# Fabric_IO.net
KiCad netlist of a schematic drawn in Altium Designer
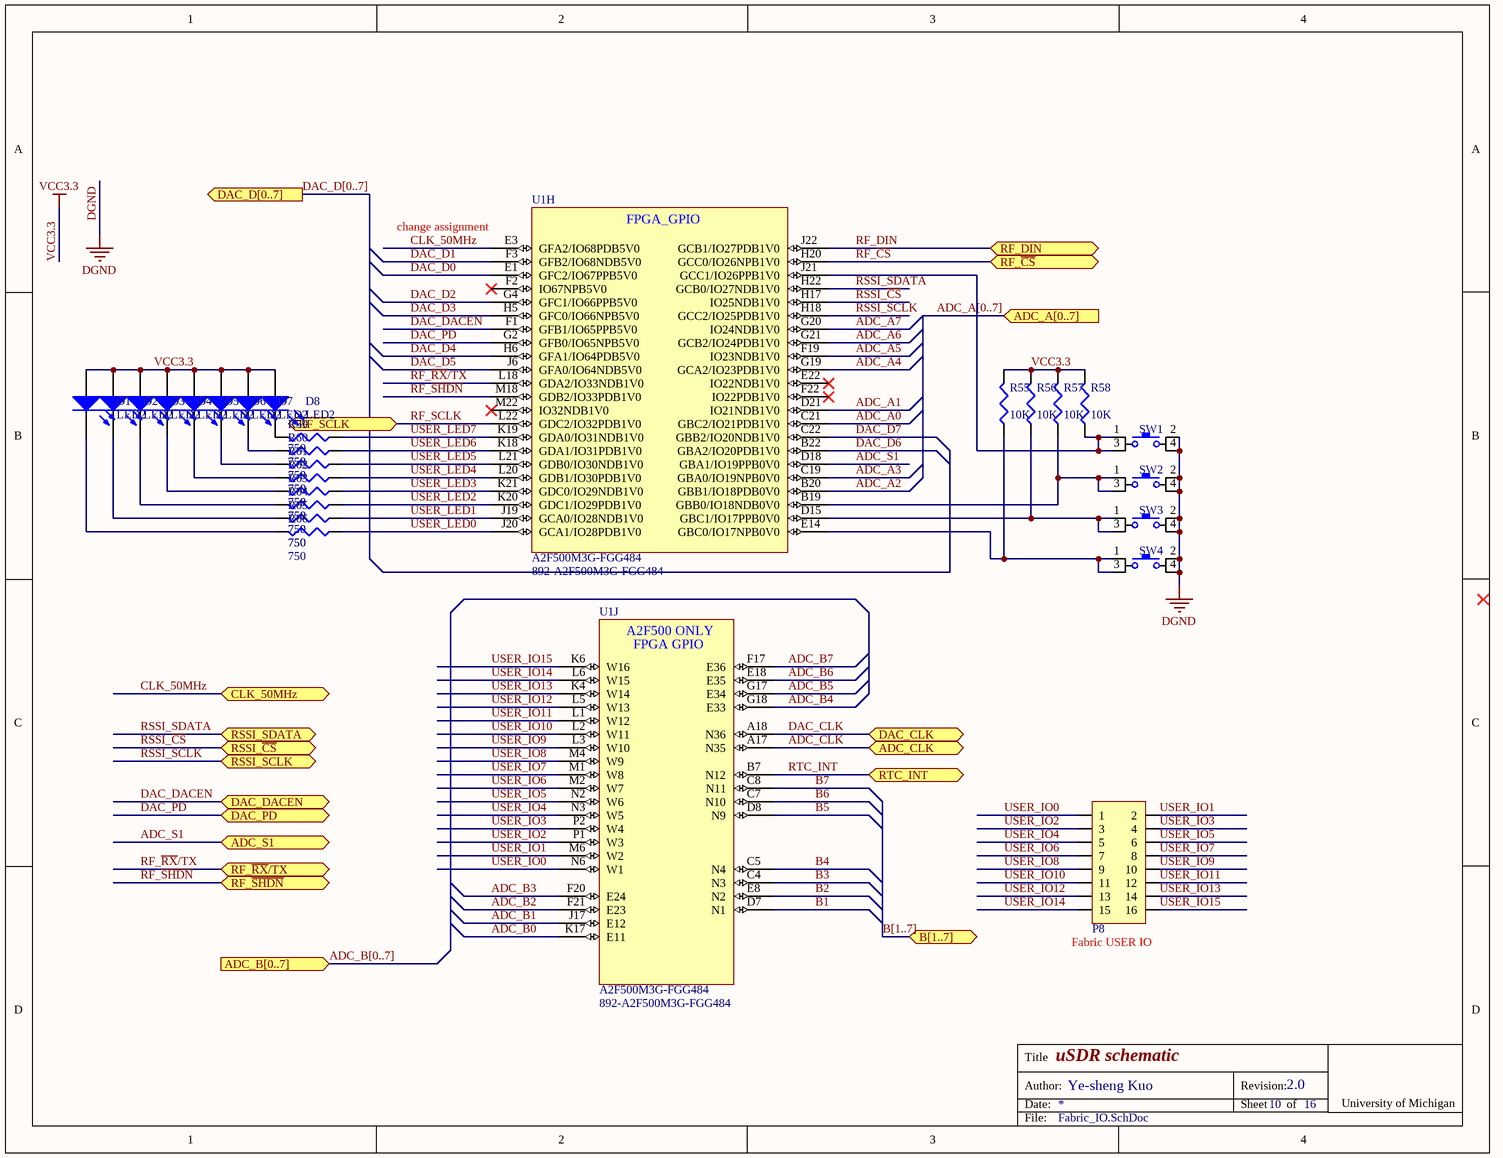
[diagram p0: Fabric_IO.SchDoc]

(export (version "E")
  (design (tool "Eeschema 10.0.6"))
  (components
    (comp (ref "D1")
      (value "LED2")
      (footprint "1608[0603]")
      (description "Typical RED, GREEN, YELLOW, AMBER GaAs LED")
      (fields (field (name "PUBLISHER") "Altium Limited"))
      (libsource (lib "Miscellaneous Devices") (part "LED Red"))
    )
    (comp (ref "D2")
      (value "LED2")
      (footprint "1608[0603]")
      (description "Typical RED, GREEN, YELLOW, AMBER GaAs LED")
      (fields (field (name "PUBLISHER") "Altium Limited"))
      (libsource (lib "Miscellaneous Devices") (part "LED Red"))
    )
    (comp (ref "D3")
      (value "LED2")
      (footprint "1608[0603]")
      (description "Typical RED, GREEN, YELLOW, AMBER GaAs LED")
      (fields (field (name "PUBLISHER") "Altium Limited"))
      (libsource (lib "Miscellaneous Devices") (part "LED Red"))
    )
    (comp (ref "D4")
      (value "LED2")
      (footprint "1608[0603]")
      (description "Typical RED, GREEN, YELLOW, AMBER GaAs LED")
      (fields (field (name "PUBLISHER") "Altium Limited"))
      (libsource (lib "Miscellaneous Devices") (part "LED Red"))
    )
    (comp (ref "D5")
      (value "LED2")
      (footprint "1608[0603]")
      (description "Typical RED, GREEN, YELLOW, AMBER GaAs LED")
      (fields (field (name "PUBLISHER") "Altium Limited"))
      (libsource (lib "Miscellaneous Devices") (part "LED Red"))
    )
    (comp (ref "D6")
      (value "LED2")
      (footprint "1608[0603]")
      (description "Typical RED, GREEN, YELLOW, AMBER GaAs LED")
      (fields (field (name "PUBLISHER") "Altium Limited"))
      (libsource (lib "Miscellaneous Devices") (part "LED Red"))
    )
    (comp (ref "D7")
      (value "LED2")
      (footprint "1608[0603]")
      (description "Typical RED, GREEN, YELLOW, AMBER GaAs LED")
      (fields (field (name "PUBLISHER") "Altium Limited"))
      (libsource (lib "Miscellaneous Devices") (part "LED Red"))
    )
    (comp (ref "D8")
      (value "LED2")
      (footprint "1608[0603]")
      (description "Typical RED, GREEN, YELLOW, AMBER GaAs LED")
      (fields (field (name "PUBLISHER") "Altium Limited"))
      (libsource (lib "Miscellaneous Devices") (part "LED Red"))
    )
    (comp (ref "P8")
      (value "2 x 8 header")
      (footprint "2x8 header")
      (description "100 mils standard header")
      (libsource (lib "SDR") (part "2 x 8 header"))
    )
    (comp (ref "R55")
      (value "10K")
      (footprint "0402")
      (description "Resistor")
      (fields (field (name "PUBLISHER") "Altium Limited"))
      (libsource (lib "Miscellaneous Devices") (part "Res3"))
    )
    (comp (ref "R56")
      (value "10K")
      (footprint "0402")
      (description "Resistor")
      (fields (field (name "PUBLISHER") "Altium Limited"))
      (libsource (lib "Miscellaneous Devices") (part "Res3"))
    )
    (comp (ref "R57")
      (value "10K")
      (footprint "0402")
      (description "Resistor")
      (fields (field (name "PUBLISHER") "Altium Limited"))
      (libsource (lib "Miscellaneous Devices") (part "Res3"))
    )
    (comp (ref "R58")
      (value "10K")
      (footprint "0402")
      (description "Resistor")
      (fields (field (name "PUBLISHER") "Altium Limited"))
      (libsource (lib "Miscellaneous Devices") (part "Res3"))
    )
    (comp (ref "R59")
      (value "750")
      (footprint "0402")
      (description "Resistor")
      (fields (field (name "ALTIUM_VALUE") "750") (field (name "PUBLISHER") "Altium Limited"))
      (libsource (lib "Miscellaneous Devices") (part "Res3"))
    )
    (comp (ref "R60")
      (value "750")
      (footprint "0402")
      (description "Resistor")
      (fields (field (name "ALTIUM_VALUE") "750") (field (name "PUBLISHER") "Altium Limited"))
      (libsource (lib "Miscellaneous Devices") (part "Res3"))
    )
    (comp (ref "R61")
      (value "750")
      (footprint "0402")
      (description "Resistor")
      (fields (field (name "ALTIUM_VALUE") "750") (field (name "PUBLISHER") "Altium Limited"))
      (libsource (lib "Miscellaneous Devices") (part "Res3"))
    )
    (comp (ref "R62")
      (value "750")
      (footprint "0402")
      (description "Resistor")
      (fields (field (name "ALTIUM_VALUE") "750") (field (name "PUBLISHER") "Altium Limited"))
      (libsource (lib "Miscellaneous Devices") (part "Res3"))
    )
    (comp (ref "R63")
      (value "750")
      (footprint "0402")
      (description "Resistor")
      (fields (field (name "ALTIUM_VALUE") "750") (field (name "PUBLISHER") "Altium Limited"))
      (libsource (lib "Miscellaneous Devices") (part "Res3"))
    )
    (comp (ref "R64")
      (value "750")
      (footprint "0402")
      (description "Resistor")
      (fields (field (name "ALTIUM_VALUE") "750") (field (name "PUBLISHER") "Altium Limited"))
      (libsource (lib "Miscellaneous Devices") (part "Res3"))
    )
    (comp (ref "R65")
      (value "750")
      (footprint "0402")
      (description "Resistor")
      (fields (field (name "ALTIUM_VALUE") "750") (field (name "PUBLISHER") "Altium Limited"))
      (libsource (lib "Miscellaneous Devices") (part "Res3"))
    )
    (comp (ref "R66")
      (value "750")
      (footprint "0402")
      (description "Resistor")
      (fields (field (name "ALTIUM_VALUE") "750") (field (name "PUBLISHER") "Altium Limited"))
      (libsource (lib "Miscellaneous Devices") (part "Res3"))
    )
    (comp (ref "SW1")
      (value "Switch 4-lead")
      (footprint "KSC403")
      (description "Switch")
      (libsource (lib "SDR") (part "Switch 4-lead"))
    )
    (comp (ref "SW2")
      (value "Switch 4-lead")
      (footprint "KSC403")
      (description "Switch")
      (libsource (lib "SDR") (part "Switch 4-lead"))
    )
    (comp (ref "SW3")
      (value "Switch 4-lead")
      (footprint "KSC403")
      (description "Switch")
      (libsource (lib "SDR") (part "Switch 4-lead"))
    )
    (comp (ref "SW4")
      (value "Switch 4-lead")
      (footprint "KSC403")
      (description "Switch")
      (libsource (lib "SDR") (part "Switch 4-lead"))
    )
    (comp (ref "U1")
      (value "A2F500M3G-FGG484")
      (footprint "BGA100P22X22-484N")
      (description "FPGA - Field Programmable Gate Array 500K System Gates")
      (fields (field (name "SUPPLIER PART NUMBER 1") "892-A2F500M3G-FGG484"))
      (libsource (lib "SDR") (part "F2-200_500-FGG484_1"))
    )
  )
  (nets
    (net (code "1") (name "/ADC_A0") (class "Default")
      (node (ref "U1") (pin "C21") (pinfunction "GBC2/IO21PDB1V0_C21") (pintype "bidirectional"))
    )
    (net (code "2") (name "/ADC_A1") (class "Default")
      (node (ref "U1") (pin "D21") (pinfunction "IO21NDB1V0_D21") (pintype "bidirectional"))
    )
    (net (code "3") (name "/ADC_A2") (class "Default")
      (node (ref "U1") (pin "B20") (pinfunction "GBB1/IO18PDB0V0_B20") (pintype "bidirectional"))
    )
    (net (code "4") (name "/ADC_A3") (class "Default")
      (node (ref "U1") (pin "C19") (pinfunction "GBA0/IO19NPB0V0_C19") (pintype "bidirectional"))
    )
    (net (code "5") (name "/ADC_A4") (class "Default")
      (node (ref "U1") (pin "G19") (pinfunction "GCA2/IO23PDB1V0_G19") (pintype "bidirectional"))
    )
    (net (code "6") (name "/ADC_A5") (class "Default")
      (node (ref "U1") (pin "F19") (pinfunction "IO23NDB1V0_F19") (pintype "bidirectional"))
    )
    (net (code "7") (name "/ADC_A6") (class "Default")
      (node (ref "U1") (pin "G21") (pinfunction "GCB2/IO24PDB1V0_G21") (pintype "bidirectional"))
    )
    (net (code "8") (name "/ADC_A7") (class "Default")
      (node (ref "U1") (pin "G20") (pinfunction "IO24NDB1V0_G20") (pintype "bidirectional"))
    )
    (net (code "10") (name "/ADC_B0") (class "Default")
      (node (ref "U1") (pin "K17") (pinfunction "E11_K17") (pintype "bidirectional"))
    )
    (net (code "11") (name "/ADC_B1") (class "Default")
      (node (ref "U1") (pin "J17") (pinfunction "E12_J17") (pintype "bidirectional"))
    )
    (net (code "12") (name "/ADC_B2") (class "Default")
      (node (ref "U1") (pin "F21") (pinfunction "E23_F21") (pintype "bidirectional"))
    )
    (net (code "13") (name "/ADC_B3") (class "Default")
      (node (ref "U1") (pin "F20") (pinfunction "E24_F20") (pintype "bidirectional"))
    )
    (net (code "14") (name "/ADC_B4") (class "Default")
      (node (ref "U1") (pin "G18") (pinfunction "E33_G18") (pintype "bidirectional"))
    )
    (net (code "15") (name "/ADC_B5") (class "Default")
      (node (ref "U1") (pin "G17") (pinfunction "E34_G17") (pintype "bidirectional"))
    )
    (net (code "16") (name "/ADC_B6") (class "Default")
      (node (ref "U1") (pin "E18") (pinfunction "E35_E18") (pintype "bidirectional"))
    )
    (net (code "17") (name "/ADC_B7") (class "Default")
      (node (ref "U1") (pin "F17") (pinfunction "E36_F17") (pintype "bidirectional"))
    )
    (net (code "19") (name "/ADC_CLK") (class "Default")
      (node (ref "U1") (pin "A17") (pinfunction "N35_A17") (pintype "bidirectional"))
    )
    (net (code "20") (name "/ADC_S1") (class "Default")
      (node (ref "U1") (pin "D18") (pinfunction "GBA1/IO19PPB0V0_D18") (pintype "bidirectional"))
    )
    (net (code "21") (name "/B1") (class "Default")
      (node (ref "U1") (pin "D7") (pinfunction "N1_D7") (pintype "bidirectional"))
    )
    (net (code "22") (name "/B2") (class "Default")
      (node (ref "U1") (pin "E8") (pinfunction "N2_E8") (pintype "bidirectional"))
    )
    (net (code "23") (name "/B3") (class "Default")
      (node (ref "U1") (pin "C4") (pinfunction "N3_C4") (pintype "bidirectional"))
    )
    (net (code "24") (name "/B4") (class "Default")
      (node (ref "U1") (pin "C5") (pinfunction "N4_C5") (pintype "bidirectional"))
    )
    (net (code "25") (name "/B5") (class "Default")
      (node (ref "U1") (pin "D8") (pinfunction "N9_D8") (pintype "bidirectional"))
    )
    (net (code "26") (name "/B6") (class "Default")
      (node (ref "U1") (pin "C7") (pinfunction "N10_C7") (pintype "bidirectional"))
    )
    (net (code "27") (name "/B7") (class "Default")
      (node (ref "U1") (pin "C8") (pinfunction "N11_C8") (pintype "bidirectional"))
    )
    (net (code "29") (name "/CLK_50MHz") (class "Default")
      (node (ref "U1") (pin "E3") (pinfunction "GFA2/IO68PDB5V0_E3") (pintype "bidirectional"))
    )
    (net (code "30") (name "/DAC_CLK") (class "Default")
      (node (ref "U1") (pin "A18") (pinfunction "N36_A18") (pintype "bidirectional"))
    )
    (net (code "31") (name "/DAC_D0") (class "Default")
      (node (ref "U1") (pin "E1") (pinfunction "GFC2/IO67PPB5V0_E1") (pintype "bidirectional"))
    )
    (net (code "32") (name "/DAC_D1") (class "Default")
      (node (ref "U1") (pin "F3") (pinfunction "GFB2/IO68NDB5V0_F3") (pintype "bidirectional"))
    )
    (net (code "33") (name "/DAC_D2") (class "Default")
      (node (ref "U1") (pin "G4") (pinfunction "GFC1/IO66PPB5V0_G4") (pintype "bidirectional"))
    )
    (net (code "34") (name "/DAC_D3") (class "Default")
      (node (ref "U1") (pin "H5") (pinfunction "GFC0/IO66NPB5V0_H5") (pintype "bidirectional"))
    )
    (net (code "35") (name "/DAC_D4") (class "Default")
      (node (ref "U1") (pin "H6") (pinfunction "GFA1/IO64PDB5V0_H6") (pintype "bidirectional"))
    )
    (net (code "36") (name "/DAC_D5") (class "Default")
      (node (ref "U1") (pin "J6") (pinfunction "GFA0/IO64NDB5V0_J6") (pintype "bidirectional"))
    )
    (net (code "37") (name "/DAC_D6") (class "Default")
      (node (ref "U1") (pin "B22") (pinfunction "GBA2/IO20PDB1V0_B22") (pintype "bidirectional"))
    )
    (net (code "38") (name "/DAC_D7") (class "Default")
      (node (ref "U1") (pin "C22") (pinfunction "GBB2/IO20NDB1V0_C22") (pintype "bidirectional"))
    )
    (net (code "39") (name "/DAC_DACEN") (class "Default")
      (node (ref "U1") (pin "F1") (pinfunction "GFB1/IO65PPB5V0_F1") (pintype "bidirectional"))
    )
    (net (code "41") (name "/DAC_PD") (class "Default")
      (node (ref "U1") (pin "G2") (pinfunction "GFB0/IO65NPB5V0_G2") (pintype "bidirectional"))
    )
    (net (code "42") (name "/RF_DIN") (class "Default")
      (node (ref "U1") (pin "J22") (pinfunction "GCB1/IO27PDB1V0_J22") (pintype "bidirectional"))
    )
    (net (code "43") (name "/RF_SCLK") (class "Default")
      (node (ref "U1") (pin "L22") (pinfunction "GDC2/IO32PDB1V0_L22") (pintype "bidirectional"))
    )
    (net (code "44") (name "/RF_~{CS}") (class "Default")
      (node (ref "U1") (pin "H20") (pinfunction "GCC0/IO26NPB1V0_H20") (pintype "bidirectional"))
    )
    (net (code "45") (name "/RF_~{RX}{slash}TX") (class "Default")
      (node (ref "U1") (pin "L18") (pinfunction "GDA2/IO33NDB1V0_L18") (pintype "bidirectional"))
    )
    (net (code "46") (name "/RF_~{SHDN}") (class "Default")
      (node (ref "U1") (pin "M18") (pinfunction "GDB2/IO33PDB1V0_M18") (pintype "bidirectional"))
    )
    (net (code "47") (name "/RSSI_SCLK") (class "Default")
      (node (ref "U1") (pin "H18") (pinfunction "GCC2/IO25PDB1V0_H18") (pintype "bidirectional"))
    )
    (net (code "48") (name "/RSSI_SDATA") (class "Default")
      (node (ref "U1") (pin "H22") (pinfunction "GCB0/IO27NDB1V0_H22") (pintype "bidirectional"))
    )
    (net (code "49") (name "/RSSI_~{CS}") (class "Default")
      (node (ref "U1") (pin "H17") (pinfunction "IO25NDB1V0_H17") (pintype "bidirectional"))
    )
    (net (code "50") (name "/RTC_INT") (class "Default")
      (node (ref "U1") (pin "B7") (pinfunction "N12_B7") (pintype "bidirectional"))
    )
    (net (code "51") (name "/USER_IO0") (class "Default")
      (node (ref "P8") (pin "1") (pinfunction "1_1") (pintype "passive"))
      (node (ref "U1") (pin "N6") (pinfunction "W1_N6") (pintype "bidirectional"))
    )
    (net (code "52") (name "/USER_IO1") (class "Default")
      (node (ref "P8") (pin "2") (pinfunction "2_2") (pintype "passive"))
      (node (ref "U1") (pin "M6") (pinfunction "W2_M6") (pintype "bidirectional"))
    )
    (net (code "53") (name "/USER_IO2") (class "Default")
      (node (ref "P8") (pin "3") (pinfunction "3_3") (pintype "passive"))
      (node (ref "U1") (pin "P1") (pinfunction "W3_P1") (pintype "bidirectional"))
    )
    (net (code "54") (name "/USER_IO3") (class "Default")
      (node (ref "P8") (pin "4") (pinfunction "4_4") (pintype "passive"))
      (node (ref "U1") (pin "P2") (pinfunction "W4_P2") (pintype "bidirectional"))
    )
    (net (code "55") (name "/USER_IO4") (class "Default")
      (node (ref "P8") (pin "5") (pinfunction "5_5") (pintype "passive"))
      (node (ref "U1") (pin "N3") (pinfunction "W5_N3") (pintype "bidirectional"))
    )
    (net (code "56") (name "/USER_IO5") (class "Default")
      (node (ref "P8") (pin "6") (pinfunction "6_6") (pintype "passive"))
      (node (ref "U1") (pin "N2") (pinfunction "W6_N2") (pintype "bidirectional"))
    )
    (net (code "57") (name "/USER_IO6") (class "Default")
      (node (ref "P8") (pin "7") (pinfunction "7_7") (pintype "passive"))
      (node (ref "U1") (pin "M2") (pinfunction "W7_M2") (pintype "bidirectional"))
    )
    (net (code "58") (name "/USER_IO7") (class "Default")
      (node (ref "P8") (pin "8") (pinfunction "8_8") (pintype "passive"))
      (node (ref "U1") (pin "M1") (pinfunction "W8_M1") (pintype "bidirectional"))
    )
    (net (code "59") (name "/USER_IO8") (class "Default")
      (node (ref "P8") (pin "9") (pinfunction "9_9") (pintype "passive"))
      (node (ref "U1") (pin "M4") (pinfunction "W9_M4") (pintype "bidirectional"))
    )
    (net (code "60") (name "/USER_IO9") (class "Default")
      (node (ref "P8") (pin "10") (pinfunction "10_10") (pintype "passive"))
      (node (ref "U1") (pin "L3") (pinfunction "W10_L3") (pintype "bidirectional"))
    )
    (net (code "61") (name "/USER_IO10") (class "Default")
      (node (ref "P8") (pin "11") (pinfunction "11_11") (pintype "passive"))
      (node (ref "U1") (pin "L2") (pinfunction "W11_L2") (pintype "bidirectional"))
    )
    (net (code "62") (name "/USER_IO11") (class "Default")
      (node (ref "P8") (pin "12") (pinfunction "12_12") (pintype "passive"))
      (node (ref "U1") (pin "L1") (pinfunction "W12_L1") (pintype "bidirectional"))
    )
    (net (code "63") (name "/USER_IO12") (class "Default")
      (node (ref "P8") (pin "13") (pinfunction "13_13") (pintype "passive"))
      (node (ref "U1") (pin "L5") (pinfunction "W13_L5") (pintype "bidirectional"))
    )
    (net (code "64") (name "/USER_IO13") (class "Default")
      (node (ref "P8") (pin "14") (pinfunction "14_14") (pintype "passive"))
      (node (ref "U1") (pin "K4") (pinfunction "W14_K4") (pintype "bidirectional"))
    )
    (net (code "65") (name "/USER_IO14") (class "Default")
      (node (ref "P8") (pin "15") (pinfunction "15_15") (pintype "passive"))
      (node (ref "U1") (pin "L6") (pinfunction "W15_L6") (pintype "bidirectional"))
    )
    (net (code "66") (name "/USER_IO15") (class "Default")
      (node (ref "P8") (pin "16") (pinfunction "16_16") (pintype "passive"))
      (node (ref "U1") (pin "K6") (pinfunction "W16_K6") (pintype "bidirectional"))
    )
    (net (code "67") (name "/USER_LED0") (class "Default")
      (node (ref "R66") (pin "1") (pinfunction "1_1") (pintype "passive"))
      (node (ref "U1") (pin "J20") (pinfunction "GCA1/IO28PDB1V0_J20") (pintype "bidirectional"))
    )
    (net (code "68") (name "/USER_LED1") (class "Default")
      (node (ref "R65") (pin "1") (pinfunction "1_1") (pintype "passive"))
      (node (ref "U1") (pin "J19") (pinfunction "GCA0/IO28NDB1V0_J19") (pintype "bidirectional"))
    )
    (net (code "69") (name "/USER_LED2") (class "Default")
      (node (ref "R64") (pin "1") (pinfunction "1_1") (pintype "passive"))
      (node (ref "U1") (pin "K20") (pinfunction "GDC1/IO29PDB1V0_K20") (pintype "bidirectional"))
    )
    (net (code "70") (name "/USER_LED3") (class "Default")
      (node (ref "R63") (pin "1") (pinfunction "1_1") (pintype "passive"))
      (node (ref "U1") (pin "K21") (pinfunction "GDC0/IO29NDB1V0_K21") (pintype "bidirectional"))
    )
    (net (code "71") (name "/USER_LED4") (class "Default")
      (node (ref "R62") (pin "1") (pinfunction "1_1") (pintype "passive"))
      (node (ref "U1") (pin "L20") (pinfunction "GDB1/IO30PDB1V0_L20") (pintype "bidirectional"))
    )
    (net (code "72") (name "/USER_LED5") (class "Default")
      (node (ref "R61") (pin "1") (pinfunction "1_1") (pintype "passive"))
      (node (ref "U1") (pin "L21") (pinfunction "GDB0/IO30NDB1V0_L21") (pintype "bidirectional"))
    )
    (net (code "73") (name "/USER_LED6") (class "Default")
      (node (ref "R60") (pin "1") (pinfunction "1_1") (pintype "passive"))
      (node (ref "U1") (pin "K18") (pinfunction "GDA1/IO31PDB1V0_K18") (pintype "bidirectional"))
    )
    (net (code "74") (name "/USER_LED7") (class "Default")
      (node (ref "R59") (pin "1") (pinfunction "1_1") (pintype "passive"))
      (node (ref "U1") (pin "K19") (pinfunction "GDA0/IO31NDB1V0_K19") (pintype "bidirectional"))
    )
    (net (code "75") (name "DGND") (class "Default")
      (node (ref "SW1") (pin "2") (pinfunction "2_2") (pintype "passive"))
      (node (ref "SW1") (pin "4") (pinfunction "4_4") (pintype "passive"))
      (node (ref "SW2") (pin "2") (pinfunction "2_2") (pintype "passive"))
      (node (ref "SW2") (pin "4") (pinfunction "4_4") (pintype "passive"))
      (node (ref "SW3") (pin "2") (pinfunction "2_2") (pintype "passive"))
      (node (ref "SW3") (pin "4") (pinfunction "4_4") (pintype "passive"))
      (node (ref "SW4") (pin "2") (pinfunction "2_2") (pintype "passive"))
      (node (ref "SW4") (pin "4") (pinfunction "4_4") (pintype "passive"))
    )
    (net (code "76") (name "Net-(D1-K)") (class "Default")
      (node (ref "D1") (pin "2") (pinfunction "K_2") (pintype "passive"))
      (node (ref "R66") (pin "2") (pinfunction "2_2") (pintype "passive"))
    )
    (net (code "77") (name "Net-(D2-K)") (class "Default")
      (node (ref "D2") (pin "2") (pinfunction "K_2") (pintype "passive"))
      (node (ref "R65") (pin "2") (pinfunction "2_2") (pintype "passive"))
    )
    (net (code "78") (name "Net-(D3-K)") (class "Default")
      (node (ref "D3") (pin "2") (pinfunction "K_2") (pintype "passive"))
      (node (ref "R64") (pin "2") (pinfunction "2_2") (pintype "passive"))
    )
    (net (code "79") (name "Net-(D4-K)") (class "Default")
      (node (ref "D4") (pin "2") (pinfunction "K_2") (pintype "passive"))
      (node (ref "R63") (pin "2") (pinfunction "2_2") (pintype "passive"))
    )
    (net (code "80") (name "Net-(D5-K)") (class "Default")
      (node (ref "D5") (pin "2") (pinfunction "K_2") (pintype "passive"))
      (node (ref "R62") (pin "2") (pinfunction "2_2") (pintype "passive"))
    )
    (net (code "81") (name "Net-(D6-K)") (class "Default")
      (node (ref "D6") (pin "2") (pinfunction "K_2") (pintype "passive"))
      (node (ref "R61") (pin "2") (pinfunction "2_2") (pintype "passive"))
    )
    (net (code "82") (name "Net-(D7-K)") (class "Default")
      (node (ref "D7") (pin "2") (pinfunction "K_2") (pintype "passive"))
      (node (ref "R60") (pin "2") (pinfunction "2_2") (pintype "passive"))
    )
    (net (code "83") (name "Net-(D8-K)") (class "Default")
      (node (ref "D8") (pin "2") (pinfunction "K_2") (pintype "passive"))
      (node (ref "R59") (pin "2") (pinfunction "2_2") (pintype "passive"))
    )
    (net (code "84") (name "Net-(U1H-GBB0{slash}IO18NDB0V0)") (class "Default")
      (node (ref "R57") (pin "1") (pinfunction "1_1") (pintype "passive"))
      (node (ref "SW2") (pin "1") (pinfunction "1_1") (pintype "passive"))
      (node (ref "SW2") (pin "3") (pinfunction "3_3") (pintype "passive"))
      (node (ref "U1") (pin "B19") (pinfunction "GBB0/IO18NDB0V0_B19") (pintype "bidirectional"))
    )
    (net (code "85") (name "Net-(U1H-GBC0{slash}IO17NPB0V0)") (class "Default")
      (node (ref "R55") (pin "1") (pinfunction "1_1") (pintype "passive"))
      (node (ref "SW4") (pin "1") (pinfunction "1_1") (pintype "passive"))
      (node (ref "SW4") (pin "3") (pinfunction "3_3") (pintype "passive"))
      (node (ref "U1") (pin "E14") (pinfunction "GBC0/IO17NPB0V0_E14") (pintype "bidirectional"))
    )
    (net (code "86") (name "Net-(U1H-GBC1{slash}IO17PPB0V0)") (class "Default")
      (node (ref "R56") (pin "1") (pinfunction "1_1") (pintype "passive"))
      (node (ref "SW3") (pin "1") (pinfunction "1_1") (pintype "passive"))
      (node (ref "SW3") (pin "3") (pinfunction "3_3") (pintype "passive"))
      (node (ref "U1") (pin "D15") (pinfunction "GBC1/IO17PPB0V0_D15") (pintype "bidirectional"))
    )
    (net (code "87") (name "Net-(U1H-GCC1{slash}IO26PPB1V0)") (class "Default")
      (node (ref "R58") (pin "1") (pinfunction "1_1") (pintype "passive"))
      (node (ref "SW1") (pin "1") (pinfunction "1_1") (pintype "passive"))
      (node (ref "SW1") (pin "3") (pinfunction "3_3") (pintype "passive"))
      (node (ref "U1") (pin "J21") (pinfunction "GCC1/IO26PPB1V0_J21") (pintype "bidirectional"))
    )
    (net (code "88") (name "VCC3.3") (class "Default")
      (node (ref "D1") (pin "1") (pinfunction "A_1") (pintype "passive"))
      (node (ref "D2") (pin "1") (pinfunction "A_1") (pintype "passive"))
      (node (ref "D3") (pin "1") (pinfunction "A_1") (pintype "passive"))
      (node (ref "D4") (pin "1") (pinfunction "A_1") (pintype "passive"))
      (node (ref "D5") (pin "1") (pinfunction "A_1") (pintype "passive"))
      (node (ref "D6") (pin "1") (pinfunction "A_1") (pintype "passive"))
      (node (ref "D7") (pin "1") (pinfunction "A_1") (pintype "passive"))
      (node (ref "D8") (pin "1") (pinfunction "A_1") (pintype "passive"))
      (node (ref "R55") (pin "2") (pinfunction "2_2") (pintype "passive"))
      (node (ref "R56") (pin "2") (pinfunction "2_2") (pintype "passive"))
      (node (ref "R57") (pin "2") (pinfunction "2_2") (pintype "passive"))
      (node (ref "R58") (pin "2") (pinfunction "2_2") (pintype "passive"))
    )
    (net (code "89") (name "unconnected-(U1H-IO22NDB1V0-PadE22)") (class "Default")
      (node (ref "U1") (pin "E22") (pinfunction "IO22NDB1V0_E22") (pintype "bidirectional+no_connect"))
    )
    (net (code "90") (name "unconnected-(U1H-IO22PDB1V0-PadF22)") (class "Default")
      (node (ref "U1") (pin "F22") (pinfunction "IO22PDB1V0_F22") (pintype "bidirectional+no_connect"))
    )
    (net (code "91") (name "unconnected-(U1H-IO32NDB1V0-PadM22)") (class "Default")
      (node (ref "U1") (pin "M22") (pinfunction "IO32NDB1V0_M22") (pintype "bidirectional+no_connect"))
    )
    (net (code "92") (name "unconnected-(U1H-IO67NPB5V0-PadF2)") (class "Default")
      (node (ref "U1") (pin "F2") (pinfunction "IO67NPB5V0_F2") (pintype "bidirectional+no_connect"))
    )
  )
)
